# ATTiny_Programmer.net
KiCad netlist of a schematic drawn in EAGLE
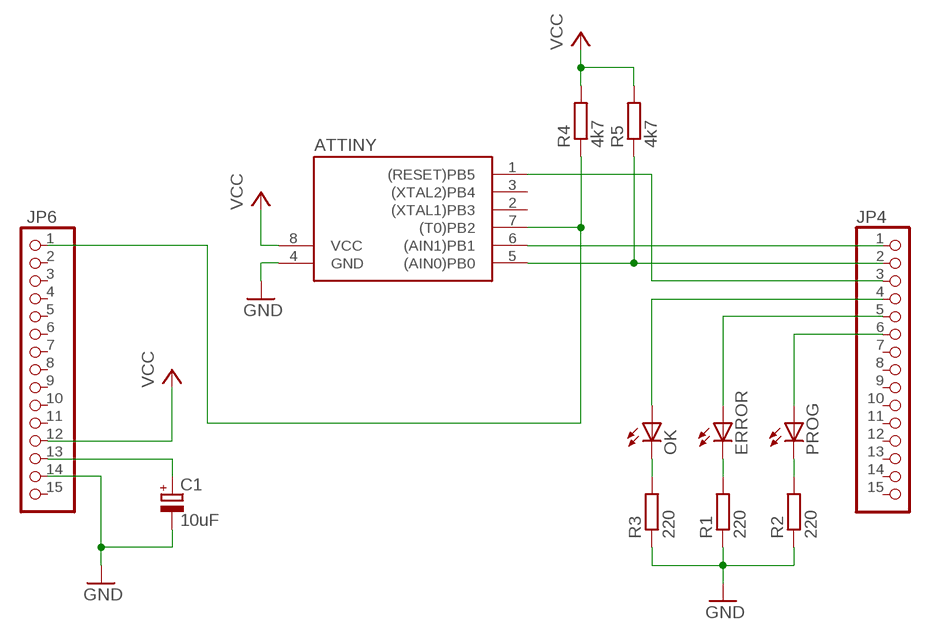
[diagram p0: schematic, sheet 1]

(export (version "E")
  (design (tool "Eeschema 10.0.6"))
  (components
    (comp (ref "ATTINY")
      (value "TINY10P")
      (footprint "eagle-import:DIL08")
      (libsource (lib "eagle-import") (part "TINY10P"))
    )
    (comp (ref "C1")
      (value "10uF")
      (footprint "eagle-import:E2-4")
      (libsource (lib "eagle-import") (part "CPOL-EUE2-4"))
    )
    (comp (ref "ERROR")
      (value "Error")
      (footprint "eagle-import:LED3MM")
      (libsource (lib "eagle-import") (part "LED3MM"))
    )
    (comp (ref "JP4")
      (value "pinheader1")
      (footprint "eagle-import:1X15")
      (libsource (lib "eagle-import") (part "PINHD-1X15"))
    )
    (comp (ref "JP6")
      (value "pinheader2")
      (footprint "eagle-import:1X15")
      (libsource (lib "eagle-import") (part "PINHD-1X15"))
    )
    (comp (ref "OK")
      (value "Ok")
      (footprint "eagle-import:LED3MM")
      (libsource (lib "eagle-import") (part "LED3MM"))
    )
    (comp (ref "PROG")
      (value "Prog")
      (footprint "eagle-import:LED3MM")
      (libsource (lib "eagle-import") (part "LED3MM"))
    )
    (comp (ref "R1")
      (value "220")
      (footprint "eagle-import:0207_7")
      (libsource (lib "eagle-import") (part "R-EU_0207/7"))
    )
    (comp (ref "R2")
      (value "220")
      (footprint "eagle-import:0207_7")
      (libsource (lib "eagle-import") (part "R-EU_0207/7"))
    )
    (comp (ref "R3")
      (value "220")
      (footprint "eagle-import:0207_7")
      (libsource (lib "eagle-import") (part "R-EU_0207/7"))
    )
    (comp (ref "R4")
      (value "4k7")
      (footprint "eagle-import:0207_7")
      (libsource (lib "eagle-import") (part "R-EU_0207/7"))
    )
    (comp (ref "R5")
      (value "4k7")
      (footprint "eagle-import:0207_7")
      (libsource (lib "eagle-import") (part "R-EU_0207/7"))
    )
  )
  (nets
    (net (code "1") (name "GND") (class "Default")
      (node (ref "ATTINY") (pin "4") (pinfunction "GND_4") (pintype "power_in"))
      (node (ref "C1") (pin "-") (pinfunction "-_-") (pintype "passive"))
      (node (ref "JP6") (pin "14") (pinfunction "14_14") (pintype "passive"))
      (node (ref "R1") (pin "1") (pinfunction "1_1") (pintype "passive"))
      (node (ref "R2") (pin "1") (pinfunction "1_1") (pintype "passive"))
      (node (ref "R3") (pin "1") (pinfunction "1_1") (pintype "passive"))
    )
    (net (code "2") (name "Net-(ATTINY-(AIN0)PB0)") (class "Default")
      (node (ref "ATTINY") (pin "5") (pinfunction "(AIN0)PB0_5") (pintype "bidirectional"))
      (node (ref "JP4") (pin "2") (pinfunction "2_2") (pintype "passive"))
      (node (ref "R5") (pin "1") (pinfunction "1_1") (pintype "passive"))
    )
    (net (code "3") (name "Net-(ATTINY-(AIN1)PB1)") (class "Default")
      (node (ref "ATTINY") (pin "6") (pinfunction "(AIN1)PB1_6") (pintype "bidirectional"))
      (node (ref "JP4") (pin "1") (pinfunction "1_1") (pintype "passive"))
    )
    (net (code "4") (name "Net-(ATTINY-(RESET)PB5)") (class "Default")
      (node (ref "ATTINY") (pin "1") (pinfunction "(RESET)PB5_1") (pintype "bidirectional"))
      (node (ref "JP4") (pin "3") (pinfunction "3_3") (pintype "passive"))
    )
    (net (code "5") (name "Net-(ATTINY-(T0)PB2)") (class "Default")
      (node (ref "ATTINY") (pin "7") (pinfunction "(T0)PB2_7") (pintype "bidirectional"))
      (node (ref "JP6") (pin "1") (pinfunction "1_1") (pintype "passive"))
      (node (ref "R4") (pin "1") (pinfunction "1_1") (pintype "passive"))
    )
    (net (code "6") (name "Net-(C1-Pad+)") (class "Default")
      (node (ref "C1") (pin "+") (pinfunction "+_+") (pintype "passive"))
      (node (ref "JP6") (pin "13") (pinfunction "13_13") (pintype "passive"))
    )
    (net (code "7") (name "Net-(ERROR-C)") (class "Default")
      (node (ref "ERROR") (pin "K") (pinfunction "C_K") (pintype "passive"))
      (node (ref "R1") (pin "2") (pinfunction "2_2") (pintype "passive"))
    )
    (net (code "8") (name "Net-(ERROR-PadA)") (class "Default")
      (node (ref "ERROR") (pin "A") (pinfunction "A_A") (pintype "passive"))
      (node (ref "JP4") (pin "5") (pinfunction "5_5") (pintype "passive"))
    )
    (net (code "9") (name "Net-(JP4-Pad4)") (class "Default")
      (node (ref "JP4") (pin "4") (pinfunction "4_4") (pintype "passive"))
      (node (ref "OK") (pin "A") (pinfunction "A_A") (pintype "passive"))
    )
    (net (code "10") (name "Net-(JP4-Pad6)") (class "Default")
      (node (ref "JP4") (pin "6") (pinfunction "6_6") (pintype "passive"))
      (node (ref "PROG") (pin "A") (pinfunction "A_A") (pintype "passive"))
    )
    (net (code "11") (name "Net-(OK-C)") (class "Default")
      (node (ref "OK") (pin "K") (pinfunction "C_K") (pintype "passive"))
      (node (ref "R3") (pin "2") (pinfunction "2_2") (pintype "passive"))
    )
    (net (code "12") (name "Net-(PROG-C)") (class "Default")
      (node (ref "PROG") (pin "K") (pinfunction "C_K") (pintype "passive"))
      (node (ref "R2") (pin "2") (pinfunction "2_2") (pintype "passive"))
    )
    (net (code "13") (name "VCC") (class "Default")
      (node (ref "ATTINY") (pin "8") (pinfunction "VCC_8") (pintype "power_in"))
      (node (ref "JP6") (pin "12") (pinfunction "12_12") (pintype "passive"))
      (node (ref "R4") (pin "2") (pinfunction "2_2") (pintype "passive"))
      (node (ref "R5") (pin "2") (pinfunction "2_2") (pintype "passive"))
    )
    (net (code "14") (name "unconnected-(ATTINY-(XTAL1)PB3-Pad2)") (class "Default")
      (node (ref "ATTINY") (pin "2") (pinfunction "(XTAL1)PB3_2") (pintype "bidirectional"))
    )
    (net (code "15") (name "unconnected-(ATTINY-(XTAL2)PB4-Pad3)") (class "Default")
      (node (ref "ATTINY") (pin "3") (pinfunction "(XTAL2)PB4_3") (pintype "bidirectional"))
    )
    (net (code "16") (name "unconnected-(JP4-Pad7)") (class "Default")
      (node (ref "JP4") (pin "7") (pinfunction "7_7") (pintype "passive"))
    )
    (net (code "17") (name "unconnected-(JP4-Pad8)") (class "Default")
      (node (ref "JP4") (pin "8") (pinfunction "8_8") (pintype "passive"))
    )
    (net (code "18") (name "unconnected-(JP4-Pad9)") (class "Default")
      (node (ref "JP4") (pin "9") (pinfunction "9_9") (pintype "passive"))
    )
    (net (code "19") (name "unconnected-(JP4-Pad10)") (class "Default")
      (node (ref "JP4") (pin "10") (pinfunction "10_10") (pintype "passive"))
    )
    (net (code "20") (name "unconnected-(JP4-Pad11)") (class "Default")
      (node (ref "JP4") (pin "11") (pinfunction "11_11") (pintype "passive"))
    )
    (net (code "21") (name "unconnected-(JP4-Pad12)") (class "Default")
      (node (ref "JP4") (pin "12") (pinfunction "12_12") (pintype "passive"))
    )
    (net (code "22") (name "unconnected-(JP4-Pad13)") (class "Default")
      (node (ref "JP4") (pin "13") (pinfunction "13_13") (pintype "passive"))
    )
    (net (code "23") (name "unconnected-(JP4-Pad14)") (class "Default")
      (node (ref "JP4") (pin "14") (pinfunction "14_14") (pintype "passive"))
    )
    (net (code "24") (name "unconnected-(JP4-Pad15)") (class "Default")
      (node (ref "JP4") (pin "15") (pinfunction "15_15") (pintype "passive"))
    )
    (net (code "25") (name "unconnected-(JP6-Pad2)") (class "Default")
      (node (ref "JP6") (pin "2") (pinfunction "2_2") (pintype "passive"))
    )
    (net (code "26") (name "unconnected-(JP6-Pad3)") (class "Default")
      (node (ref "JP6") (pin "3") (pinfunction "3_3") (pintype "passive"))
    )
    (net (code "27") (name "unconnected-(JP6-Pad4)") (class "Default")
      (node (ref "JP6") (pin "4") (pinfunction "4_4") (pintype "passive"))
    )
    (net (code "28") (name "unconnected-(JP6-Pad5)") (class "Default")
      (node (ref "JP6") (pin "5") (pinfunction "5_5") (pintype "passive"))
    )
    (net (code "29") (name "unconnected-(JP6-Pad6)") (class "Default")
      (node (ref "JP6") (pin "6") (pinfunction "6_6") (pintype "passive"))
    )
    (net (code "30") (name "unconnected-(JP6-Pad7)") (class "Default")
      (node (ref "JP6") (pin "7") (pinfunction "7_7") (pintype "passive"))
    )
    (net (code "31") (name "unconnected-(JP6-Pad8)") (class "Default")
      (node (ref "JP6") (pin "8") (pinfunction "8_8") (pintype "passive"))
    )
    (net (code "32") (name "unconnected-(JP6-Pad9)") (class "Default")
      (node (ref "JP6") (pin "9") (pinfunction "9_9") (pintype "passive"))
    )
    (net (code "33") (name "unconnected-(JP6-Pad10)") (class "Default")
      (node (ref "JP6") (pin "10") (pinfunction "10_10") (pintype "passive"))
    )
    (net (code "34") (name "unconnected-(JP6-Pad11)") (class "Default")
      (node (ref "JP6") (pin "11") (pinfunction "11_11") (pintype "passive"))
    )
    (net (code "35") (name "unconnected-(JP6-Pad15)") (class "Default")
      (node (ref "JP6") (pin "15") (pinfunction "15_15") (pintype "passive"))
    )
  )
)
